# ethernet.net
KiCad netlist of a schematic drawn in Altium Designer
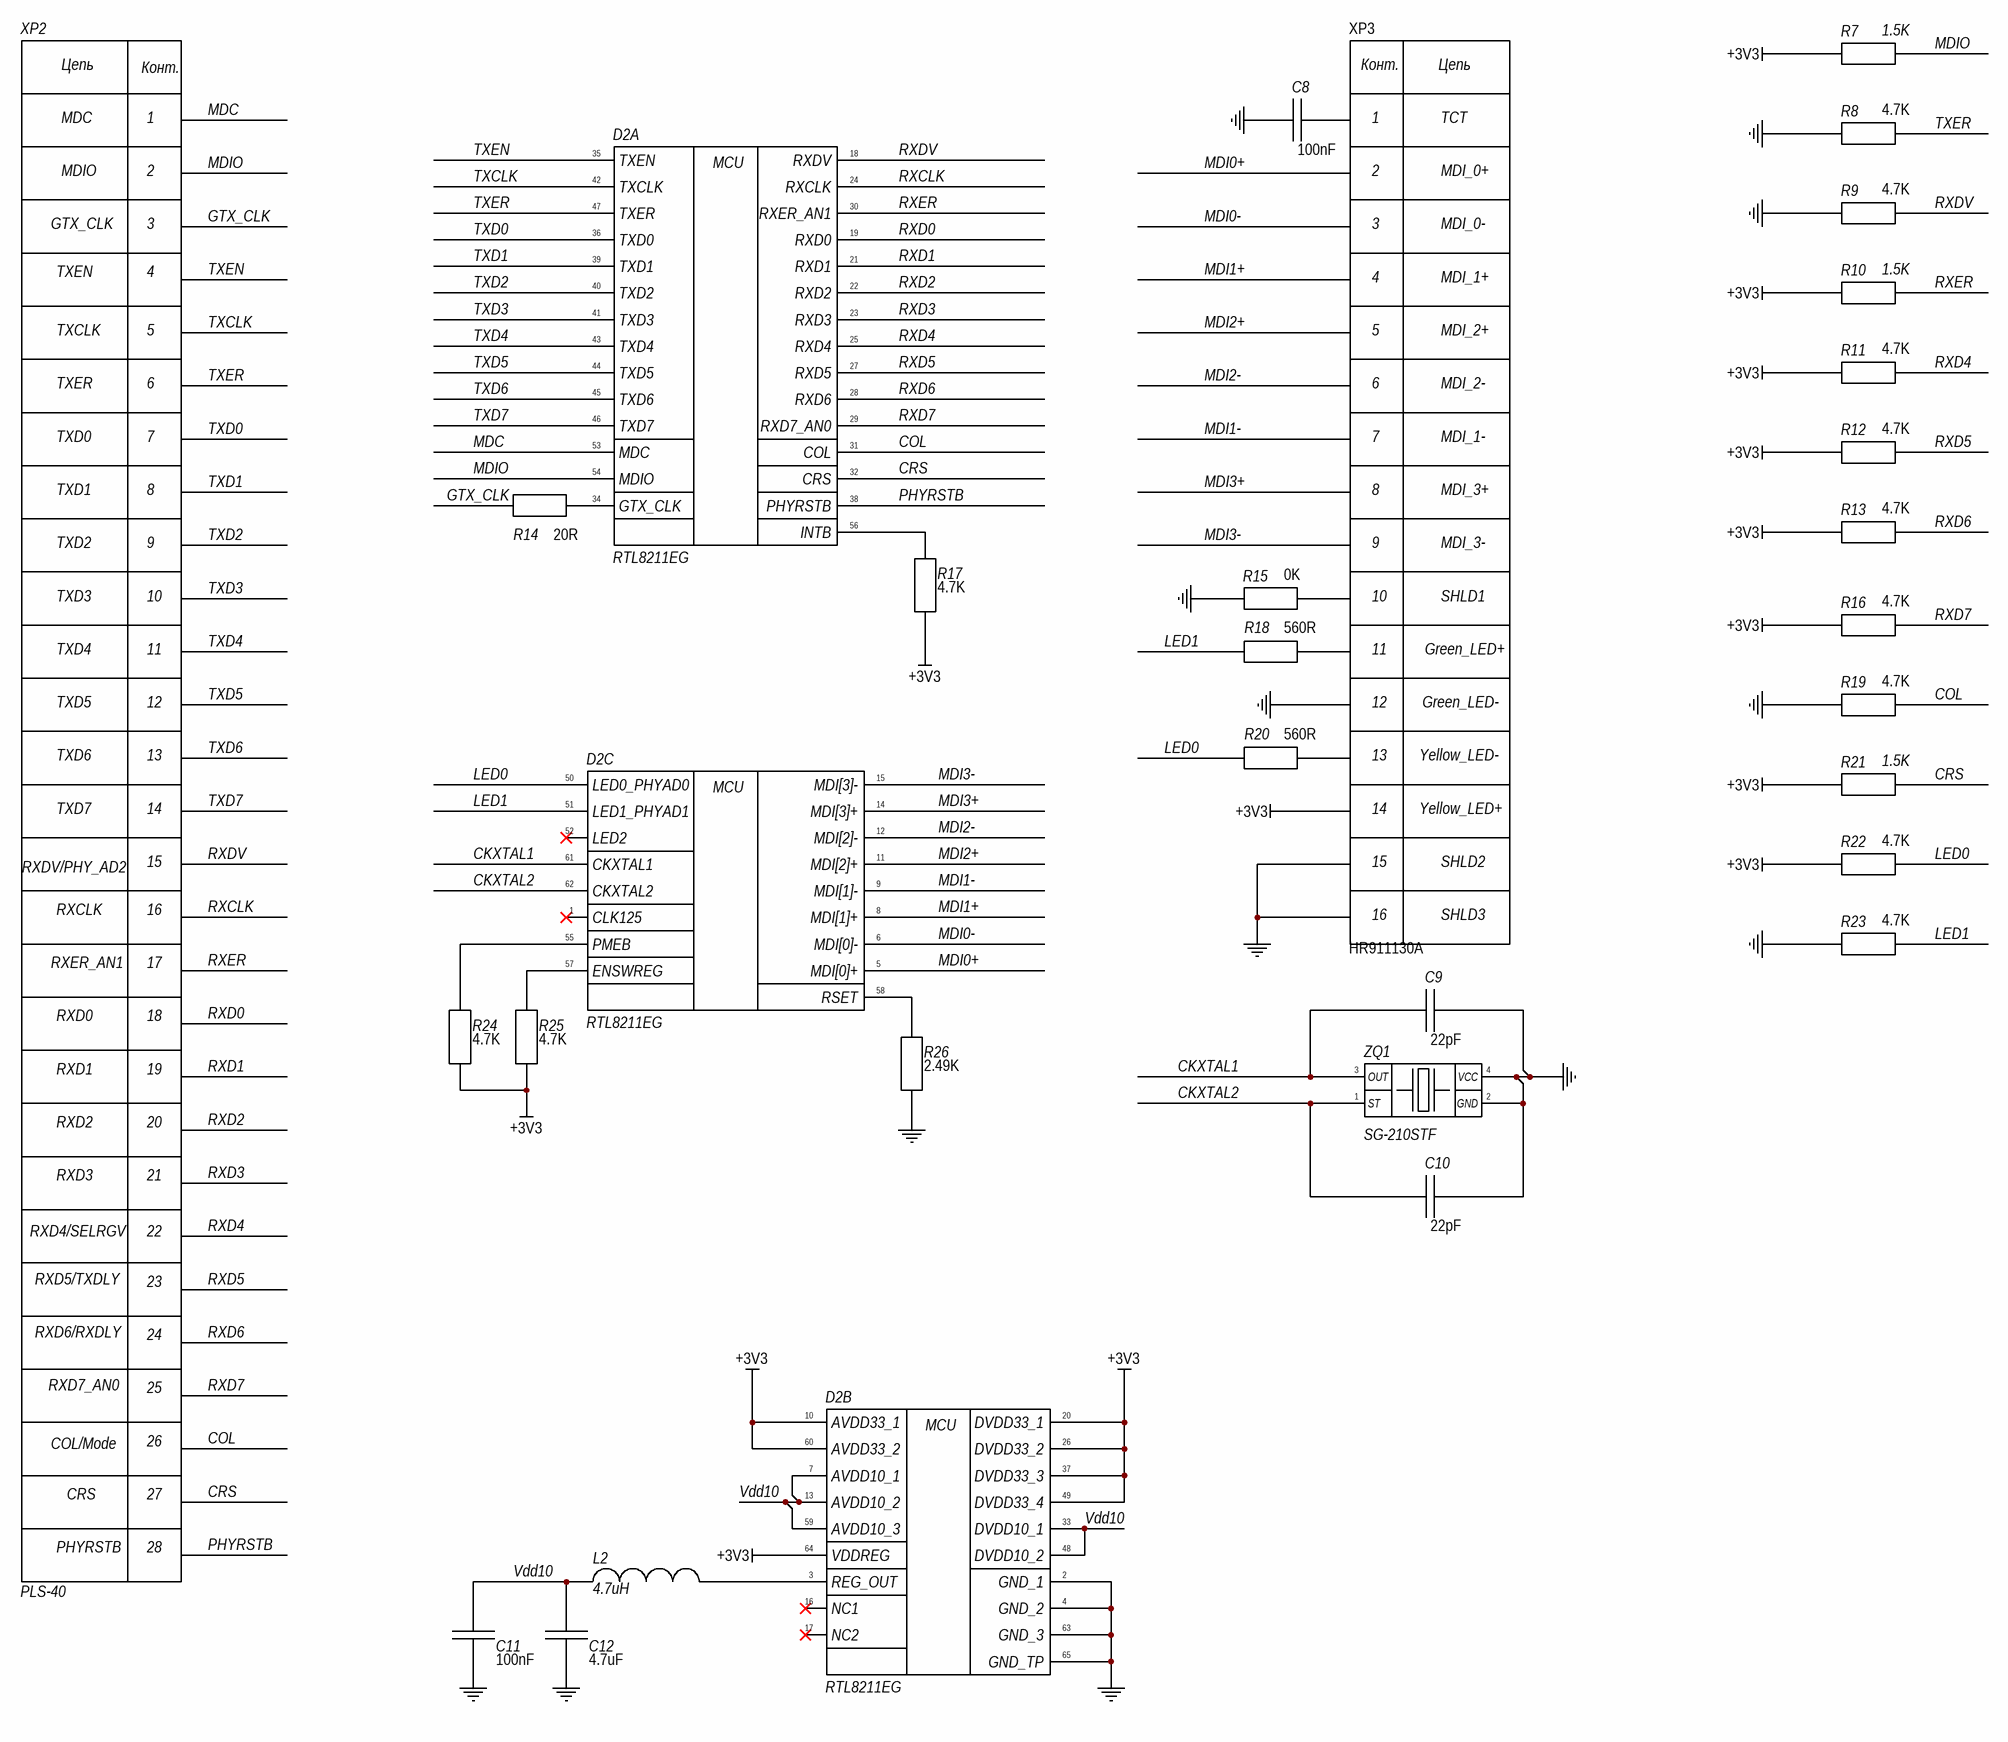
[diagram p0: ethernet.SchDoc]

(export (version "E")
  (design (tool "Eeschema 10.0.6"))
  (components
    (comp (ref "C8")
      (value "100nF")
      (footprint "SMD 0805")
      (description "Конденсатор номиналом 1.5 nF")
      (libsource (lib "Capacitors") (part "100nF"))
    )
    (comp (ref "C9")
      (value "22pF")
      (footprint "SMD 0805")
      (description "Конденсатор номиналом 22 pF")
      (libsource (lib "Capacitors") (part "22pF"))
    )
    (comp (ref "C10")
      (value "22pF")
      (footprint "SMD 0805")
      (description "Конденсатор номиналом 22 pF")
      (libsource (lib "Capacitors") (part "22pF"))
    )
    (comp (ref "C11")
      (value "100nF")
      (footprint "SMD 0805")
      (description "Конденсатор номиналом 1.5 nF")
      (libsource (lib "Capacitors") (part "100nF"))
    )
    (comp (ref "C12")
      (value "4.7uF")
      (footprint "SMD 0805")
      (description "Конденсатор номиналом 4.7 uF")
      (libsource (lib "Capacitors") (part "4.7uF"))
    )
    (comp (ref "D2")
      (value "RTL8211EG")
      (footprint "Logic:QFN50P900X900X100_HS-65N")
      (libsource (lib "Logic") (part "RTL8211EG"))
    )
    (comp (ref "L2")
      (value "4.7uH")
      (footprint "SP43-4R7M")
      (description "Катушка индуктивности 4.7 мкГн")
      (libsource (lib "Inductors & Transformers") (part "4.7u"))
    )
    (comp (ref "R7")
      (value "1.5K")
      (footprint "RESC0805")
      (description "Резистор номиналом 1.5 кОм")
      (libsource (lib "Resistors") (part "1.5K"))
    )
    (comp (ref "R8")
      (value "4.7K")
      (footprint "RESC0805")
      (description "Резистор номиналом 4.7 кОм")
      (libsource (lib "Resistors") (part "4.7K"))
    )
    (comp (ref "R9")
      (value "4.7K")
      (footprint "RESC0805")
      (description "Резистор номиналом 4.7 кОм")
      (libsource (lib "Resistors") (part "4.7K"))
    )
    (comp (ref "R10")
      (value "1.5K")
      (footprint "RESC0805")
      (description "Резистор номиналом 1.5 кОм")
      (libsource (lib "Resistors") (part "1.5K"))
    )
    (comp (ref "R11")
      (value "4.7K")
      (footprint "RESC0805")
      (description "Резистор номиналом 4.7 кОм")
      (libsource (lib "Resistors") (part "4.7K"))
    )
    (comp (ref "R12")
      (value "4.7K")
      (footprint "RESC0805")
      (description "Резистор номиналом 4.7 кОм")
      (libsource (lib "Resistors") (part "4.7K"))
    )
    (comp (ref "R13")
      (value "4.7K")
      (footprint "RESC0805")
      (description "Резистор номиналом 4.7 кОм")
      (libsource (lib "Resistors") (part "4.7K"))
    )
    (comp (ref "R14")
      (value "20R")
      (footprint "RESC0805")
      (description "Резистор номиналом 20 Ом")
      (libsource (lib "Resistors") (part "20R"))
    )
    (comp (ref "R15")
      (value "0K")
      (footprint "RESC0805")
      (description "Резистор номиналом 0 Ом")
      (libsource (lib "Resistors") (part "0K"))
    )
    (comp (ref "R16")
      (value "4.7K")
      (footprint "RESC0805")
      (description "Резистор номиналом 4.7 кОм")
      (libsource (lib "Resistors") (part "4.7K"))
    )
    (comp (ref "R17")
      (value "4.7K")
      (footprint "RESC0805")
      (description "Резистор номиналом 4.7 кОм")
      (libsource (lib "Resistors") (part "4.7K"))
    )
    (comp (ref "R18")
      (value "560R")
      (footprint "RESC0805")
      (description "Резистор номиналом 560 Ом")
      (libsource (lib "Resistors") (part "560R"))
    )
    (comp (ref "R19")
      (value "4.7K")
      (footprint "RESC0805")
      (description "Резистор номиналом 4.7 кОм")
      (libsource (lib "Resistors") (part "4.7K"))
    )
    (comp (ref "R20")
      (value "560R")
      (footprint "RESC0805")
      (description "Резистор номиналом 560 Ом")
      (libsource (lib "Resistors") (part "560R"))
    )
    (comp (ref "R21")
      (value "1.5K")
      (footprint "RESC0805")
      (description "Резистор номиналом 1.5 кОм")
      (libsource (lib "Resistors") (part "1.5K"))
    )
    (comp (ref "R22")
      (value "4.7K")
      (footprint "RESC0805")
      (description "Резистор номиналом 4.7 кОм")
      (libsource (lib "Resistors") (part "4.7K"))
    )
    (comp (ref "R23")
      (value "4.7K")
      (footprint "RESC0805")
      (description "Резистор номиналом 4.7 кОм")
      (libsource (lib "Resistors") (part "4.7K"))
    )
    (comp (ref "R24")
      (value "4.7K")
      (footprint "RESC0805")
      (description "Резистор номиналом 4.7 кОм")
      (libsource (lib "Resistors") (part "4.7K"))
    )
    (comp (ref "R25")
      (value "4.7K")
      (footprint "RESC0805")
      (description "Резистор номиналом 4.7 кОм")
      (libsource (lib "Resistors") (part "4.7K"))
    )
    (comp (ref "R26")
      (value "2.49K")
      (footprint "RESC0805")
      (description "Резистор номиналом 2.49 кОм")
      (libsource (lib "Resistors") (part "2.49K"))
    )
    (comp (ref "XP2")
      (value "PLS-40")
      (footprint "PBD-28")
      (description "Служит для подключения разрабатываемой платы")
      (libsource (lib "Connectors") (part "SMT_FPGA"))
    )
    (comp (ref "XP3")
      (value "HR911130A")
      (footprint "Connectors:HR911130A")
      (description "Разъём RJ45 с встроенными трансформаторами и индикацией, 10/100Base-T Ethernet (HR911130A)")
      (libsource (lib "Connectors") (part "RJ-45"))
    )
    (comp (ref "ZQ1")
      (value "SG-210STF")
      (footprint "SG-210STF")
      (libsource (lib "Crystals & Oscillators") (part "SG-210STF"))
    )
  )
  (nets
    (net (code "1") (name "+3V3") (class "Default")
      (node (ref "D2") (pin "10") (pinfunction "AVDD33_1_10") (pintype "passive"))
      (node (ref "D2") (pin "20") (pinfunction "DVDD33_1_20") (pintype "passive"))
      (node (ref "D2") (pin "26") (pinfunction "DVDD33_2_26") (pintype "passive"))
      (node (ref "D2") (pin "37") (pinfunction "DVDD33_3_37") (pintype "passive"))
      (node (ref "D2") (pin "49") (pinfunction "DVDD33_4_49") (pintype "passive"))
      (node (ref "D2") (pin "60") (pinfunction "AVDD33_2_60") (pintype "passive"))
      (node (ref "D2") (pin "64") (pinfunction "VDDREG_64") (pintype "passive"))
      (node (ref "R10") (pin "1") (pinfunction "1_1") (pintype "passive"))
      (node (ref "R11") (pin "1") (pinfunction "1_1") (pintype "passive"))
      (node (ref "R12") (pin "1") (pinfunction "1_1") (pintype "passive"))
      (node (ref "R13") (pin "1") (pinfunction "1_1") (pintype "passive"))
      (node (ref "R16") (pin "1") (pinfunction "1_1") (pintype "passive"))
      (node (ref "R17") (pin "1") (pinfunction "1_1") (pintype "passive"))
      (node (ref "R21") (pin "1") (pinfunction "1_1") (pintype "passive"))
      (node (ref "R22") (pin "1") (pinfunction "1_1") (pintype "passive"))
      (node (ref "R24") (pin "1") (pinfunction "1_1") (pintype "passive"))
      (node (ref "R25") (pin "1") (pinfunction "1_1") (pintype "passive"))
      (node (ref "R7") (pin "1") (pinfunction "1_1") (pintype "passive"))
      (node (ref "XP3") (pin "14") (pinfunction "14_14") (pintype "passive"))
    )
    (net (code "2") (name "/CKXTAL1") (class "Default")
      (node (ref "C9") (pin "1") (pinfunction "1_1") (pintype "passive"))
      (node (ref "D2") (pin "61") (pinfunction "CKXTAL1_61") (pintype "passive"))
      (node (ref "ZQ1") (pin "3") (pinfunction "OUT_3") (pintype "passive"))
    )
    (net (code "3") (name "/CKXTAL2") (class "Default")
      (node (ref "C10") (pin "1") (pinfunction "1_1") (pintype "passive"))
      (node (ref "D2") (pin "62") (pinfunction "CKXTAL2_62") (pintype "passive"))
      (node (ref "ZQ1") (pin "1") (pinfunction "ST_1") (pintype "passive"))
    )
    (net (code "4") (name "/COL") (class "Default")
      (node (ref "D2") (pin "31") (pinfunction "COL_31") (pintype "passive"))
      (node (ref "R19") (pin "2") (pinfunction "2_2") (pintype "passive"))
      (node (ref "XP2") (pin "26") (pinfunction "26_26") (pintype "passive"))
    )
    (net (code "5") (name "/CRS") (class "Default")
      (node (ref "D2") (pin "32") (pinfunction "CRS_32") (pintype "passive"))
      (node (ref "R21") (pin "2") (pinfunction "2_2") (pintype "passive"))
      (node (ref "XP2") (pin "27") (pinfunction "27_27") (pintype "passive"))
    )
    (net (code "6") (name "/GTX_CLK") (class "Default")
      (node (ref "R14") (pin "1") (pinfunction "1_1") (pintype "passive"))
      (node (ref "XP2") (pin "3") (pinfunction "3_3") (pintype "passive"))
    )
    (net (code "7") (name "/LED0") (class "Default")
      (node (ref "D2") (pin "50") (pinfunction "LED0_PHYAD0_50") (pintype "passive"))
      (node (ref "R20") (pin "1") (pinfunction "1_1") (pintype "passive"))
      (node (ref "R22") (pin "2") (pinfunction "2_2") (pintype "passive"))
    )
    (net (code "8") (name "/LED1") (class "Default")
      (node (ref "D2") (pin "51") (pinfunction "LED1_PHYAD1_51") (pintype "passive"))
      (node (ref "R18") (pin "1") (pinfunction "1_1") (pintype "passive"))
      (node (ref "R23") (pin "2") (pinfunction "2_2") (pintype "passive"))
    )
    (net (code "9") (name "/MDC") (class "Default")
      (node (ref "D2") (pin "53") (pinfunction "MDC_53") (pintype "passive"))
      (node (ref "XP2") (pin "1") (pinfunction "1_1") (pintype "passive"))
    )
    (net (code "10") (name "/MDI0+") (class "Default")
      (node (ref "D2") (pin "5") (pinfunction "MDI[0]+_5") (pintype "passive"))
      (node (ref "XP3") (pin "2") (pinfunction "2_2") (pintype "passive"))
    )
    (net (code "11") (name "/MDI0-") (class "Default")
      (node (ref "D2") (pin "6") (pinfunction "MDI[0]-_6") (pintype "passive"))
      (node (ref "XP3") (pin "3") (pinfunction "3_3") (pintype "passive"))
    )
    (net (code "12") (name "/MDI1+") (class "Default")
      (node (ref "D2") (pin "8") (pinfunction "MDI[1]+_8") (pintype "passive"))
      (node (ref "XP3") (pin "4") (pinfunction "4_4") (pintype "passive"))
    )
    (net (code "13") (name "/MDI1-") (class "Default")
      (node (ref "D2") (pin "9") (pinfunction "MDI[1]-_9") (pintype "passive"))
      (node (ref "XP3") (pin "7") (pinfunction "7_7") (pintype "passive"))
    )
    (net (code "14") (name "/MDI2+") (class "Default")
      (node (ref "D2") (pin "11") (pinfunction "MDI[2]+_11") (pintype "passive"))
      (node (ref "XP3") (pin "5") (pinfunction "5_5") (pintype "passive"))
    )
    (net (code "15") (name "/MDI2-") (class "Default")
      (node (ref "D2") (pin "12") (pinfunction "MDI[2]-_12") (pintype "passive"))
      (node (ref "XP3") (pin "6") (pinfunction "6_6") (pintype "passive"))
    )
    (net (code "16") (name "/MDI3+") (class "Default")
      (node (ref "D2") (pin "14") (pinfunction "MDI[3]+_14") (pintype "passive"))
      (node (ref "XP3") (pin "8") (pinfunction "8_8") (pintype "passive"))
    )
    (net (code "17") (name "/MDI3-") (class "Default")
      (node (ref "D2") (pin "15") (pinfunction "MDI[3]-_15") (pintype "passive"))
      (node (ref "XP3") (pin "9") (pinfunction "9_9") (pintype "passive"))
    )
    (net (code "18") (name "/MDIO") (class "Default")
      (node (ref "D2") (pin "54") (pinfunction "MDIO_54") (pintype "passive"))
      (node (ref "R7") (pin "2") (pinfunction "2_2") (pintype "passive"))
      (node (ref "XP2") (pin "2") (pinfunction "2_2") (pintype "passive"))
    )
    (net (code "19") (name "/PHYRSTB") (class "Default")
      (node (ref "D2") (pin "38") (pinfunction "PHYRSTB_38") (pintype "passive"))
      (node (ref "XP2") (pin "28") (pinfunction "28_28") (pintype "passive"))
    )
    (net (code "20") (name "/RXCLK") (class "Default")
      (node (ref "D2") (pin "24") (pinfunction "RXCLK_24") (pintype "passive"))
      (node (ref "XP2") (pin "16") (pinfunction "16_16") (pintype "passive"))
    )
    (net (code "21") (name "/RXD0") (class "Default")
      (node (ref "D2") (pin "19") (pinfunction "RXD0_19") (pintype "passive"))
      (node (ref "XP2") (pin "18") (pinfunction "18_18") (pintype "passive"))
    )
    (net (code "22") (name "/RXD1") (class "Default")
      (node (ref "D2") (pin "21") (pinfunction "RXD1_21") (pintype "passive"))
      (node (ref "XP2") (pin "19") (pinfunction "19_19") (pintype "passive"))
    )
    (net (code "23") (name "/RXD2") (class "Default")
      (node (ref "D2") (pin "22") (pinfunction "RXD2_22") (pintype "passive"))
      (node (ref "XP2") (pin "20") (pinfunction "20_20") (pintype "passive"))
    )
    (net (code "24") (name "/RXD3") (class "Default")
      (node (ref "D2") (pin "23") (pinfunction "RXD3_23") (pintype "passive"))
      (node (ref "XP2") (pin "21") (pinfunction "21_21") (pintype "passive"))
    )
    (net (code "25") (name "/RXD4") (class "Default")
      (node (ref "D2") (pin "25") (pinfunction "RXD4_25") (pintype "passive"))
      (node (ref "R11") (pin "2") (pinfunction "2_2") (pintype "passive"))
      (node (ref "XP2") (pin "22") (pinfunction "22_22") (pintype "passive"))
    )
    (net (code "26") (name "/RXD5") (class "Default")
      (node (ref "D2") (pin "27") (pinfunction "RXD5_27") (pintype "passive"))
      (node (ref "R12") (pin "2") (pinfunction "2_2") (pintype "passive"))
      (node (ref "XP2") (pin "23") (pinfunction "23_23") (pintype "passive"))
    )
    (net (code "27") (name "/RXD6") (class "Default")
      (node (ref "D2") (pin "28") (pinfunction "RXD6_28") (pintype "passive"))
      (node (ref "R13") (pin "2") (pinfunction "2_2") (pintype "passive"))
      (node (ref "XP2") (pin "24") (pinfunction "24_24") (pintype "passive"))
    )
    (net (code "28") (name "/RXD7") (class "Default")
      (node (ref "D2") (pin "29") (pinfunction "RXD7_AN0_29") (pintype "passive"))
      (node (ref "R16") (pin "2") (pinfunction "2_2") (pintype "passive"))
      (node (ref "XP2") (pin "25") (pinfunction "25_25") (pintype "passive"))
    )
    (net (code "29") (name "/RXDV") (class "Default")
      (node (ref "D2") (pin "18") (pinfunction "RXDV_18") (pintype "passive"))
      (node (ref "R9") (pin "2") (pinfunction "2_2") (pintype "passive"))
      (node (ref "XP2") (pin "15") (pinfunction "15_15") (pintype "passive"))
    )
    (net (code "30") (name "/RXER") (class "Default")
      (node (ref "D2") (pin "30") (pinfunction "RXER_AN1_30") (pintype "passive"))
      (node (ref "R10") (pin "2") (pinfunction "2_2") (pintype "passive"))
      (node (ref "XP2") (pin "17") (pinfunction "17_17") (pintype "passive"))
    )
    (net (code "31") (name "/TXCLK") (class "Default")
      (node (ref "D2") (pin "42") (pinfunction "TXCLK_42") (pintype "passive"))
      (node (ref "XP2") (pin "5") (pinfunction "5_5") (pintype "passive"))
    )
    (net (code "32") (name "/TXD0") (class "Default")
      (node (ref "D2") (pin "36") (pinfunction "TXD0_36") (pintype "passive"))
      (node (ref "XP2") (pin "7") (pinfunction "7_7") (pintype "passive"))
    )
    (net (code "33") (name "/TXD1") (class "Default")
      (node (ref "D2") (pin "39") (pinfunction "TXD1_39") (pintype "passive"))
      (node (ref "XP2") (pin "8") (pinfunction "8_8") (pintype "passive"))
    )
    (net (code "34") (name "/TXD2") (class "Default")
      (node (ref "D2") (pin "40") (pinfunction "TXD2_40") (pintype "passive"))
      (node (ref "XP2") (pin "9") (pinfunction "9_9") (pintype "passive"))
    )
    (net (code "35") (name "/TXD3") (class "Default")
      (node (ref "D2") (pin "41") (pinfunction "TXD3_41") (pintype "passive"))
      (node (ref "XP2") (pin "10") (pinfunction "10_10") (pintype "passive"))
    )
    (net (code "36") (name "/TXD4") (class "Default")
      (node (ref "D2") (pin "43") (pinfunction "TXD4_43") (pintype "passive"))
      (node (ref "XP2") (pin "11") (pinfunction "11_11") (pintype "passive"))
    )
    (net (code "37") (name "/TXD5") (class "Default")
      (node (ref "D2") (pin "44") (pinfunction "TXD5_44") (pintype "passive"))
      (node (ref "XP2") (pin "12") (pinfunction "12_12") (pintype "passive"))
    )
    (net (code "38") (name "/TXD6") (class "Default")
      (node (ref "D2") (pin "45") (pinfunction "TXD6_45") (pintype "passive"))
      (node (ref "XP2") (pin "13") (pinfunction "13_13") (pintype "passive"))
    )
    (net (code "39") (name "/TXD7") (class "Default")
      (node (ref "D2") (pin "46") (pinfunction "TXD7_46") (pintype "passive"))
      (node (ref "XP2") (pin "14") (pinfunction "14_14") (pintype "passive"))
    )
    (net (code "40") (name "/TXEN") (class "Default")
      (node (ref "D2") (pin "35") (pinfunction "TXEN_35") (pintype "passive"))
      (node (ref "XP2") (pin "4") (pinfunction "4_4") (pintype "passive"))
    )
    (net (code "41") (name "/TXER") (class "Default")
      (node (ref "D2") (pin "47") (pinfunction "TXER_47") (pintype "passive"))
      (node (ref "R8") (pin "2") (pinfunction "2_2") (pintype "passive"))
      (node (ref "XP2") (pin "6") (pinfunction "6_6") (pintype "passive"))
    )
    (net (code "42") (name "/Vdd10") (class "Default")
      (node (ref "C11") (pin "2") (pinfunction "2_2") (pintype "passive"))
      (node (ref "C12") (pin "2") (pinfunction "2_2") (pintype "passive"))
      (node (ref "D2") (pin "13") (pinfunction "AVDD10_2_13") (pintype "passive"))
      (node (ref "D2") (pin "33") (pinfunction "DVDD10_1_33") (pintype "passive"))
      (node (ref "D2") (pin "48") (pinfunction "DVDD10_2_48") (pintype "passive"))
      (node (ref "D2") (pin "59") (pinfunction "AVDD10_3_59") (pintype "passive"))
      (node (ref "D2") (pin "7") (pinfunction "AVDD10_1_7") (pintype "passive"))
      (node (ref "L2") (pin "1") (pinfunction "1_1") (pintype "passive"))
    )
    (net (code "43") (name "GND") (class "Default")
      (node (ref "C10") (pin "2") (pinfunction "2_2") (pintype "passive"))
      (node (ref "C11") (pin "1") (pinfunction "1_1") (pintype "passive"))
      (node (ref "C12") (pin "1") (pinfunction "1_1") (pintype "passive"))
      (node (ref "C8") (pin "1") (pinfunction "1_1") (pintype "passive"))
      (node (ref "C9") (pin "2") (pinfunction "2_2") (pintype "passive"))
      (node (ref "D2") (pin "2") (pinfunction "GND_1_2") (pintype "passive"))
      (node (ref "D2") (pin "4") (pinfunction "GND_2_4") (pintype "passive"))
      (node (ref "D2") (pin "63") (pinfunction "GND_3_63") (pintype "passive"))
      (node (ref "D2") (pin "65") (pinfunction "GND_TP_65") (pintype "passive"))
      (node (ref "R15") (pin "1") (pinfunction "1_1") (pintype "passive"))
      (node (ref "R19") (pin "1") (pinfunction "1_1") (pintype "passive"))
      (node (ref "R23") (pin "1") (pinfunction "1_1") (pintype "passive"))
      (node (ref "R26") (pin "1") (pinfunction "1_1") (pintype "passive"))
      (node (ref "R8") (pin "1") (pinfunction "1_1") (pintype "passive"))
      (node (ref "R9") (pin "1") (pinfunction "1_1") (pintype "passive"))
      (node (ref "XP3") (pin "12") (pinfunction "12_12") (pintype "passive"))
      (node (ref "XP3") (pin "15") (pinfunction "15_15") (pintype "passive"))
      (node (ref "XP3") (pin "16") (pinfunction "16_16") (pintype "passive"))
      (node (ref "ZQ1") (pin "2") (pinfunction "GND_2") (pintype "passive"))
      (node (ref "ZQ1") (pin "4") (pinfunction "VCC_4") (pintype "passive"))
    )
    (net (code "44") (name "Net-(C8-Pad2)") (class "Default")
      (node (ref "C8") (pin "2") (pinfunction "2_2") (pintype "passive"))
      (node (ref "XP3") (pin "1") (pinfunction "1_1") (pintype "passive"))
    )
    (net (code "45") (name "Net-(D2A-GTX_CLK)") (class "Default")
      (node (ref "D2") (pin "34") (pinfunction "GTX_CLK_34") (pintype "passive"))
      (node (ref "R14") (pin "2") (pinfunction "2_2") (pintype "passive"))
    )
    (net (code "46") (name "Net-(D2A-INTB)") (class "Default")
      (node (ref "D2") (pin "56") (pinfunction "INTB_56") (pintype "passive"))
      (node (ref "R17") (pin "2") (pinfunction "2_2") (pintype "passive"))
    )
    (net (code "47") (name "Net-(D2B-REG_OUT)") (class "Default")
      (node (ref "D2") (pin "3") (pinfunction "REG_OUT_3") (pintype "passive"))
      (node (ref "L2") (pin "2") (pinfunction "2_2") (pintype "passive"))
    )
    (net (code "48") (name "Net-(D2C-ENSWREG)") (class "Default")
      (node (ref "D2") (pin "57") (pinfunction "ENSWREG_57") (pintype "passive"))
      (node (ref "R25") (pin "2") (pinfunction "2_2") (pintype "passive"))
    )
    (net (code "49") (name "Net-(D2C-PMEB)") (class "Default")
      (node (ref "D2") (pin "55") (pinfunction "PMEB_55") (pintype "passive"))
      (node (ref "R24") (pin "2") (pinfunction "2_2") (pintype "passive"))
    )
    (net (code "50") (name "Net-(D2C-RSET)") (class "Default")
      (node (ref "D2") (pin "58") (pinfunction "RSET_58") (pintype "passive"))
      (node (ref "R26") (pin "2") (pinfunction "2_2") (pintype "passive"))
    )
    (net (code "51") (name "Net-(R15-Pad2)") (class "Default")
      (node (ref "R15") (pin "2") (pinfunction "2_2") (pintype "passive"))
      (node (ref "XP3") (pin "10") (pinfunction "10_10") (pintype "passive"))
    )
    (net (code "52") (name "Net-(R18-Pad2)") (class "Default")
      (node (ref "R18") (pin "2") (pinfunction "2_2") (pintype "passive"))
      (node (ref "XP3") (pin "11") (pinfunction "11_11") (pintype "passive"))
    )
    (net (code "53") (name "Net-(R20-Pad2)") (class "Default")
      (node (ref "R20") (pin "2") (pinfunction "2_2") (pintype "passive"))
      (node (ref "XP3") (pin "13") (pinfunction "13_13") (pintype "passive"))
    )
    (net (code "54") (name "unconnected-(D2B-NC1-Pad16)") (class "Default")
      (node (ref "D2") (pin "16") (pinfunction "NC1_16") (pintype "passive+no_connect"))
    )
    (net (code "55") (name "unconnected-(D2B-NC2-Pad17)") (class "Default")
      (node (ref "D2") (pin "17") (pinfunction "NC2_17") (pintype "passive+no_connect"))
    )
    (net (code "56") (name "unconnected-(D2C-CLK125-Pad1)") (class "Default")
      (node (ref "D2") (pin "1") (pinfunction "CLK125_1") (pintype "passive+no_connect"))
    )
    (net (code "57") (name "unconnected-(D2C-LED2-Pad52)") (class "Default")
      (node (ref "D2") (pin "52") (pinfunction "LED2_52") (pintype "passive+no_connect"))
    )
  )
)
